# scheme3.net
KiCad netlist of a schematic drawn in EAGLE
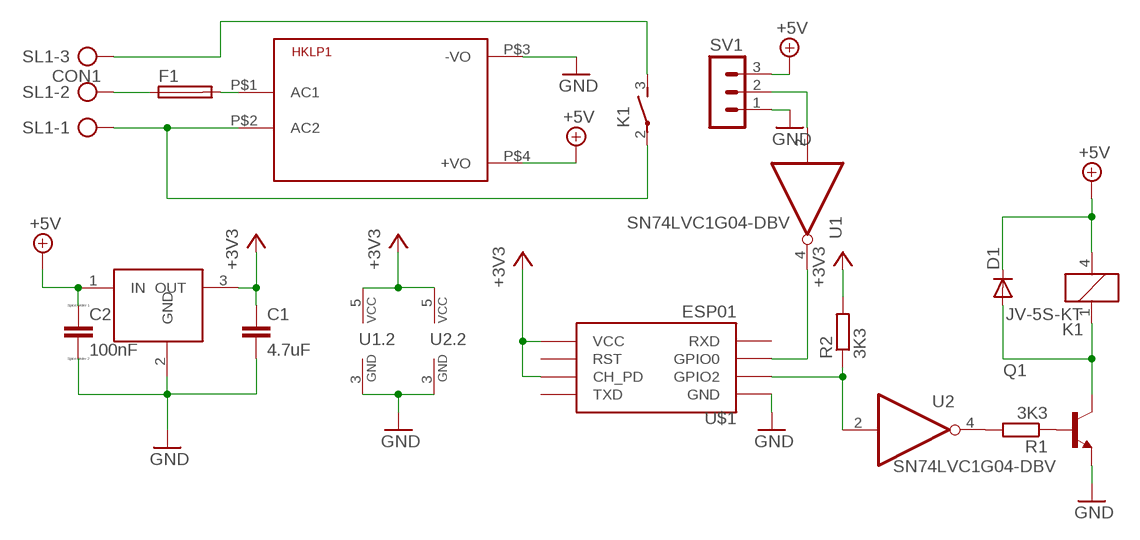
[diagram p0: schematic, sheet 1]

(export (version "E")
  (design (tool "Eeschema 10.0.6"))
  (components
    (comp (ref "C1")
      (value "4.7uF")
      (footprint "eagle-import:C0805")
      (libsource (lib "eagle-import") (part "C-EUC0805"))
    )
    (comp (ref "C2")
      (value "100nF")
      (footprint "eagle-import:C0603")
      (libsource (lib "eagle-import") (part "CC0603"))
    )
    (comp (ref "D1")
      (value "D-SOD123")
      (footprint "eagle-import:SOD123")
      (libsource (lib "eagle-import") (part "D-SOD123"))
    )
    (comp (ref "F1")
      (value "TE5")
      (footprint "eagle-import:TE5")
      (libsource (lib "eagle-import") (part "TE5"))
    )
    (comp (ref "HKLP1")
      (value "HKLPM01")
      (footprint "eagle-import:HKLPM01")
      (libsource (lib "eagle-import") (part "HKLPM01"))
    )
    (comp (ref "K1")
      (value "JV-5S-KT")
      (footprint "eagle-import:JV-KT")
      (libsource (lib "eagle-import") (part "JV-KT-5S"))
    )
    (comp (ref "Q1")
      (value "BC817-16-NPN-SOT23-BEC")
      (footprint "eagle-import:SOT23-BEC")
      (libsource (lib "eagle-import") (part "-NPN-SOT23-BECBC817-16"))
    )
    (comp (ref "R1")
      (value "3K3")
      (footprint "eagle-import:R0603")
      (libsource (lib "eagle-import") (part "R-EU_R0603"))
    )
    (comp (ref "R2")
      (value "3K3")
      (footprint "eagle-import:R0603")
      (libsource (lib "eagle-import") (part "R-EU_R0603"))
    )
    (comp (ref "SL1")
      (value "CON1")
      (footprint "eagle-import:AK300_3")
      (libsource (lib "eagle-import") (part "AK300/3"))
    )
    (comp (ref "SV1")
      (value "MA03-1")
      (footprint "eagle-import:MA03-1")
      (libsource (lib "eagle-import") (part "MA03-1"))
    )
    (comp (ref "U$1")
      (value "ESP01")
      (footprint "eagle-import:ESP01")
      (libsource (lib "eagle-import") (part "ESP01"))
    )
    (comp (ref "U$2")
      (value "LF33CV")
      (footprint "eagle-import:TO220V")
      (libsource (lib "eagle-import") (part "LF33CV"))
    )
    (comp (ref "U1")
      (value "SN74LVC1G04-DBV")
      (footprint "eagle-import:SOT23-5")
      (libsource (lib "eagle-import") (part "SN74LVC1G04-DBV"))
    )
    (comp (ref "U2")
      (value "SN74LVC1G04-DBV")
      (footprint "eagle-import:SOT23-5")
      (libsource (lib "eagle-import") (part "SN74LVC1G04-DBV"))
    )
  )
  (nets
    (net (code "1") (name "+3V3") (class "Default")
      (node (ref "C1") (pin "1") (pinfunction "1_1") (pintype "passive"))
      (node (ref "R2") (pin "2") (pinfunction "2_2") (pintype "passive"))
      (node (ref "U$1") (pin "CH_PD") (pinfunction "CH_PD_CH_PD") (pintype "bidirectional"))
      (node (ref "U$1") (pin "VCC") (pinfunction "VCC_VCC") (pintype "bidirectional"))
      (node (ref "U$2") (pin "3") (pinfunction "OUT_3") (pintype "bidirectional"))
      (node (ref "U1") (pin "5") (pinfunction "VCC_5") (pintype "power_in"))
      (node (ref "U2") (pin "5") (pinfunction "VCC_5") (pintype "power_in"))
    )
    (net (code "2") (name "+5V") (class "Default")
      (node (ref "C2") (pin "1") (pinfunction "1_1") (pintype "passive"))
      (node (ref "D1") (pin "1") (pinfunction "C_1") (pintype "passive"))
      (node (ref "HKLP1") (pin "P$4") (pinfunction "+VO_P$4") (pintype "bidirectional"))
      (node (ref "K1") (pin "4") (pinfunction "2_4") (pintype "passive"))
      (node (ref "SV1") (pin "3") (pinfunction "3_3") (pintype "passive"))
      (node (ref "U$2") (pin "1") (pinfunction "IN_1") (pintype "bidirectional"))
    )
    (net (code "3") (name "GND") (class "Default")
      (node (ref "C1") (pin "2") (pinfunction "2_2") (pintype "passive"))
      (node (ref "C2") (pin "2") (pinfunction "2_2") (pintype "passive"))
      (node (ref "HKLP1") (pin "P$3") (pinfunction "-VO_P$3") (pintype "bidirectional"))
      (node (ref "Q1") (pin "E") (pinfunction "E_E") (pintype "passive"))
      (node (ref "SV1") (pin "1") (pinfunction "1_1") (pintype "passive"))
      (node (ref "U$1") (pin "GND") (pinfunction "GND_GND") (pintype "bidirectional"))
      (node (ref "U$2") (pin "2") (pinfunction "GND_2") (pintype "bidirectional"))
      (node (ref "U1") (pin "3") (pinfunction "GND_3") (pintype "power_in"))
      (node (ref "U2") (pin "3") (pinfunction "GND_3") (pintype "power_in"))
    )
    (net (code "4") (name "Net-(D1-A)") (class "Default")
      (node (ref "D1") (pin "2") (pinfunction "A_2") (pintype "passive"))
      (node (ref "K1") (pin "1") (pinfunction "1_1") (pintype "passive"))
      (node (ref "Q1") (pin "C") (pinfunction "C_C") (pintype "passive"))
    )
    (net (code "5") (name "Net-(HKLP1-AC1)") (class "Default")
      (node (ref "F1") (pin "2") (pinfunction "2_2") (pintype "passive"))
      (node (ref "HKLP1") (pin "P$1") (pinfunction "AC1_P$1") (pintype "bidirectional"))
    )
    (net (code "6") (name "Net-(HKLP1-AC2)") (class "Default")
      (node (ref "HKLP1") (pin "P$2") (pinfunction "AC2_P$2") (pintype "bidirectional"))
      (node (ref "K1") (pin "2") (pinfunction "P_2") (pintype "passive"))
      (node (ref "SL1") (pin "1") (pinfunction "KL_1") (pintype "passive"))
    )
    (net (code "7") (name "Net-(K1B-S)") (class "Default")
      (node (ref "K1") (pin "3") (pinfunction "S_3") (pintype "passive"))
      (node (ref "SL1") (pin "3") (pinfunction "KL_3") (pintype "passive"))
    )
    (net (code "8") (name "Net-(Q1-PadB)") (class "Default")
      (node (ref "Q1") (pin "B") (pinfunction "B_B") (pintype "passive"))
      (node (ref "R1") (pin "1") (pinfunction "1_1") (pintype "passive"))
    )
    (net (code "9") (name "Net-(SL1B-KL)") (class "Default")
      (node (ref "F1") (pin "1") (pinfunction "1_1") (pintype "passive"))
      (node (ref "SL1") (pin "2") (pinfunction "KL_2") (pintype "passive"))
    )
    (net (code "10") (name "Net-(U1A-A)") (class "Default")
      (node (ref "SV1") (pin "2") (pinfunction "2_2") (pintype "passive"))
      (node (ref "U1") (pin "2") (pinfunction "A_2") (pintype "input"))
    )
    (net (code "11") (name "Net-(U1A-Y)") (class "Default")
      (node (ref "U$1") (pin "GPIO0") (pinfunction "GPIO0_GPIO0") (pintype "bidirectional"))
      (node (ref "U1") (pin "4") (pinfunction "Y_4") (pintype "output"))
    )
    (net (code "12") (name "Net-(U2A-A)") (class "Default")
      (node (ref "R2") (pin "1") (pinfunction "1_1") (pintype "passive"))
      (node (ref "U$1") (pin "GPIO2") (pinfunction "GPIO2_GPIO2") (pintype "bidirectional"))
      (node (ref "U2") (pin "2") (pinfunction "A_2") (pintype "input"))
    )
    (net (code "13") (name "Net-(U2A-Y)") (class "Default")
      (node (ref "R1") (pin "2") (pinfunction "2_2") (pintype "passive"))
      (node (ref "U2") (pin "4") (pinfunction "Y_4") (pintype "output"))
    )
    (net (code "14") (name "unconnected-(U$1-PadRST)") (class "Default")
      (node (ref "U$1") (pin "RST") (pinfunction "RST_RST") (pintype "bidirectional"))
    )
    (net (code "15") (name "unconnected-(U$1-RXD-PadRX)") (class "Default")
      (node (ref "U$1") (pin "RX") (pinfunction "RXD_RX") (pintype "bidirectional"))
    )
    (net (code "16") (name "unconnected-(U$1-TXD-PadTX)") (class "Default")
      (node (ref "U$1") (pin "TX") (pinfunction "TXD_TX") (pintype "bidirectional"))
    )
  )
)
